# PCB_Node.net
KiCad netlist of a schematic drawn in EAGLE
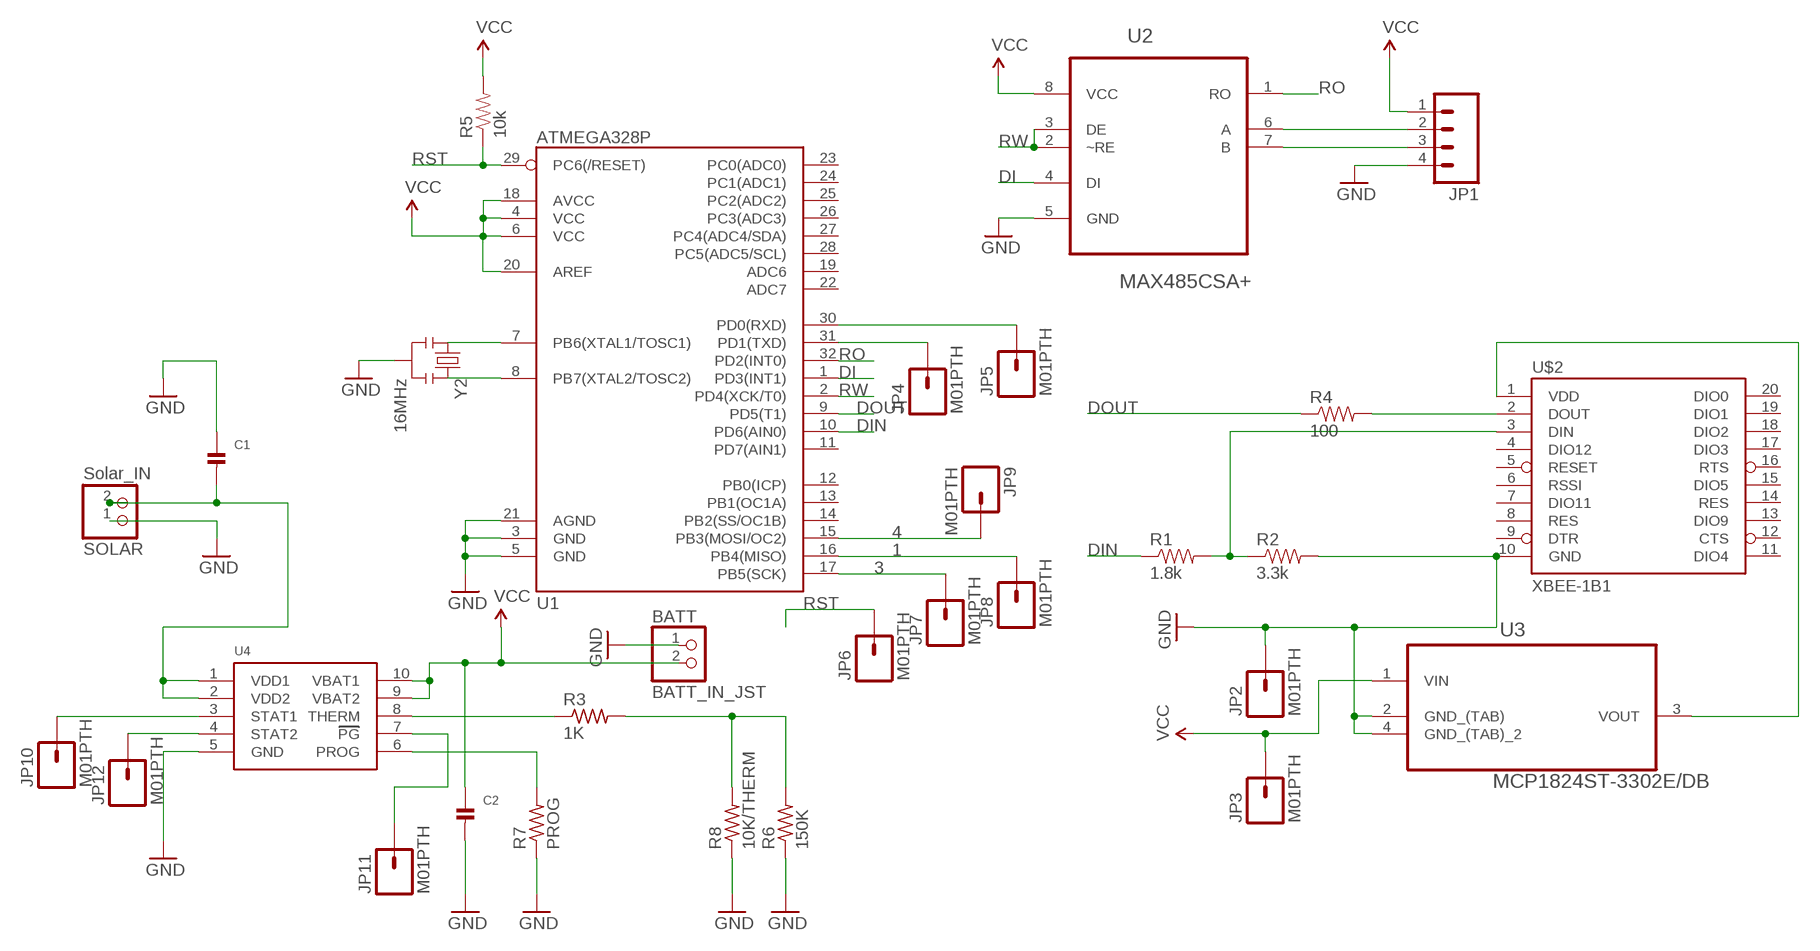
[diagram p0: schematic, sheet 1]

(export (version "E")
  (design (tool "Eeschema 10.0.6"))
  (components
    (comp (ref "BATT")
      (value "BATT_IN_JST")
      (footprint "eagle-import:JSTPH2")
      (libsource (lib "eagle-import") (part "JST_2PIN"))
    )
    (comp (ref "C1")
      (value "CAP_CERAMIC0805")
      (footprint "eagle-import:0805")
      (libsource (lib "eagle-import") (part "CAP_CERAMIC0805"))
    )
    (comp (ref "C2")
      (value "CAP_CERAMIC0805")
      (footprint "eagle-import:0805")
      (libsource (lib "eagle-import") (part "CAP_CERAMIC0805"))
    )
    (comp (ref "JP1")
      (value "M04PTH")
      (footprint "eagle-import:1X04")
      (libsource (lib "eagle-import") (part "M04PTH"))
    )
    (comp (ref "JP2")
      (value "M01PTH")
      (footprint "eagle-import:1X01")
      (libsource (lib "eagle-import") (part "M01PTH"))
    )
    (comp (ref "JP3")
      (value "M01PTH")
      (footprint "eagle-import:1X01")
      (libsource (lib "eagle-import") (part "M01PTH"))
    )
    (comp (ref "JP4")
      (value "M01PTH")
      (footprint "eagle-import:1X01")
      (libsource (lib "eagle-import") (part "M01PTH"))
    )
    (comp (ref "JP5")
      (value "M01PTH")
      (footprint "eagle-import:1X01")
      (libsource (lib "eagle-import") (part "M01PTH"))
    )
    (comp (ref "JP6")
      (value "M01PTH")
      (footprint "eagle-import:1X01")
      (libsource (lib "eagle-import") (part "M01PTH"))
    )
    (comp (ref "JP7")
      (value "M01PTH")
      (footprint "eagle-import:1X01")
      (libsource (lib "eagle-import") (part "M01PTH"))
    )
    (comp (ref "JP8")
      (value "M01PTH")
      (footprint "eagle-import:1X01")
      (libsource (lib "eagle-import") (part "M01PTH"))
    )
    (comp (ref "JP9")
      (value "M01PTH")
      (footprint "eagle-import:1X01")
      (libsource (lib "eagle-import") (part "M01PTH"))
    )
    (comp (ref "JP10")
      (value "M01PTH")
      (footprint "eagle-import:1X01")
      (libsource (lib "eagle-import") (part "M01PTH"))
    )
    (comp (ref "JP11")
      (value "M01PTH")
      (footprint "eagle-import:1X01")
      (libsource (lib "eagle-import") (part "M01PTH"))
    )
    (comp (ref "JP12")
      (value "M01PTH")
      (footprint "eagle-import:1X01")
      (libsource (lib "eagle-import") (part "M01PTH"))
    )
    (comp (ref "R1")
      (value "1.8k")
      (footprint "eagle-import:0603-RES")
      (libsource (lib "eagle-import") (part "1.8KOHM1/10W1%(0603)"))
    )
    (comp (ref "R2")
      (value "3.3k")
      (footprint "eagle-import:0603-RES")
      (libsource (lib "eagle-import") (part "3.3KOHM1/10W1%(0603)"))
    )
    (comp (ref "R3")
      (value "1K")
      (footprint "eagle-import:R0805")
      (libsource (lib "eagle-import") (part "R-US_R0805"))
    )
    (comp (ref "R4")
      (value "100")
      (footprint "eagle-import:0603-RES")
      (libsource (lib "eagle-import") (part "100OHM1/10W1%(0603)"))
    )
    (comp (ref "R5")
      (value "10k")
      (footprint "eagle-import:0603-RES")
      (libsource (lib "eagle-import") (part "10K-1%RES-00824"))
    )
    (comp (ref "R6")
      (value "150K")
      (footprint "eagle-import:R0805")
      (libsource (lib "eagle-import") (part "R-US_R0805"))
    )
    (comp (ref "R7")
      (value "PROG")
      (footprint "eagle-import:0805-THM")
      (libsource (lib "eagle-import") (part "RESISTOR_DUAL"))
    )
    (comp (ref "R8")
      (value "10K/THERM")
      (footprint "eagle-import:0805-THM")
      (libsource (lib "eagle-import") (part "R-US_FLIPFLOP"))
    )
    (comp (ref "SOLAR")
      (value "Solar_IN")
      (footprint "eagle-import:JSTPH2")
      (libsource (lib "eagle-import") (part "JST_2PIN"))
    )
    (comp (ref "U$2")
      (value "XBEE-1B1")
      (footprint "eagle-import:XBEE-1")
      (libsource (lib "eagle-import") (part "XBEE-1B1"))
    )
    (comp (ref "U1")
      (value "ATMEGA328P")
      (footprint "eagle-import:TQFP32-08")
      (libsource (lib "eagle-import") (part "ATMEGA328_SMT"))
    )
    (comp (ref "U2")
      (value "MAX485CSA+")
      (footprint "eagle-import:SOIC127P600X175-8N")
      (libsource (lib "eagle-import") (part "MAX485CSA+"))
    )
    (comp (ref "U3")
      (value "MCP1824ST-3302E/DB")
      (footprint "eagle-import:SOT230P700X180-4N")
      (libsource (lib "eagle-import") (part "MCP1824ST-3302E/DB"))
    )
    (comp (ref "U4")
      (value "MCP73833")
      (footprint "eagle-import:MSOP10")
      (libsource (lib "eagle-import") (part "MCP73833"))
    )
    (comp (ref "Y2")
      (value "16MHz")
      (footprint "eagle-import:RESONATOR-SMD")
      (libsource (lib "eagle-import") (part "RESONATOR16MHZ"))
    )
  )
  (nets
    (net (code "1") (name "/1") (class "Default")
      (node (ref "JP8") (pin "1") (pinfunction "1_1") (pintype "passive"))
      (node (ref "U1") (pin "16") (pinfunction "PB4(MISO)_16") (pintype "bidirectional"))
    )
    (net (code "2") (name "/3") (class "Default")
      (node (ref "JP7") (pin "1") (pinfunction "1_1") (pintype "passive"))
      (node (ref "U1") (pin "17") (pinfunction "PB5(SCK)_17") (pintype "bidirectional"))
    )
    (net (code "3") (name "/4") (class "Default")
      (node (ref "JP9") (pin "1") (pinfunction "1_1") (pintype "passive"))
      (node (ref "U1") (pin "15") (pinfunction "PB3(MOSI/OC2)_15") (pintype "bidirectional"))
    )
    (net (code "4") (name "/DI") (class "Default")
      (node (ref "U1") (pin "1") (pinfunction "PD3(INT1)_1") (pintype "bidirectional"))
      (node (ref "U2") (pin "4") (pinfunction "DI_4") (pintype "input"))
    )
    (net (code "5") (name "/DIN") (class "Default")
      (node (ref "R1") (pin "1") (pinfunction "1_1") (pintype "passive"))
      (node (ref "U1") (pin "10") (pinfunction "PD6(AIN0)_10") (pintype "bidirectional"))
    )
    (net (code "6") (name "/DOUT") (class "Default")
      (node (ref "R4") (pin "1") (pinfunction "1_1") (pintype "passive"))
      (node (ref "U1") (pin "9") (pinfunction "PD5(T1)_9") (pintype "bidirectional"))
    )
    (net (code "7") (name "/RO") (class "Default")
      (node (ref "U1") (pin "32") (pinfunction "PD2(INT0)_32") (pintype "bidirectional"))
      (node (ref "U2") (pin "1") (pinfunction "RO_1") (pintype "output"))
    )
    (net (code "8") (name "/RST") (class "Default")
      (node (ref "JP6") (pin "1") (pinfunction "1_1") (pintype "passive"))
      (node (ref "R5") (pin "1") (pinfunction "1_1") (pintype "passive"))
      (node (ref "U1") (pin "29") (pinfunction "PC6(/RESET)_29") (pintype "bidirectional"))
    )
    (net (code "9") (name "/RW") (class "Default")
      (node (ref "U1") (pin "2") (pinfunction "PD4(XCK/T0)_2") (pintype "bidirectional"))
      (node (ref "U2") (pin "2") (pinfunction "~{RE}_2") (pintype "input"))
      (node (ref "U2") (pin "3") (pinfunction "DE_3") (pintype "input"))
    )
    (net (code "10") (name "GND") (class "Default")
      (node (ref "BATT") (pin "1") (pinfunction "1_1") (pintype "passive"))
      (node (ref "C1") (pin "1") (pinfunction "P$1_1") (pintype "passive"))
      (node (ref "C2") (pin "2") (pinfunction "P$2_2") (pintype "passive"))
      (node (ref "JP1") (pin "4") (pinfunction "4_4") (pintype "passive"))
      (node (ref "JP2") (pin "1") (pinfunction "1_1") (pintype "passive"))
      (node (ref "R2") (pin "2") (pinfunction "2_2") (pintype "passive"))
      (node (ref "R6") (pin "1") (pinfunction "1_1") (pintype "passive"))
      (node (ref "R7") (pin "1") (pinfunction "1_1") (pintype "passive"))
      (node (ref "R8") (pin "1") (pinfunction "1_1") (pintype "passive"))
      (node (ref "SOLAR") (pin "1") (pinfunction "1_1") (pintype "passive"))
      (node (ref "U$2") (pin "10") (pinfunction "GND_10") (pintype "power_in"))
      (node (ref "U1") (pin "21") (pinfunction "AGND_21") (pintype "bidirectional"))
      (node (ref "U1") (pin "3") (pinfunction "GND_3") (pintype "bidirectional"))
      (node (ref "U1") (pin "5") (pinfunction "GND_5") (pintype "bidirectional"))
      (node (ref "U2") (pin "5") (pinfunction "GND_5") (pintype "passive"))
      (node (ref "U3") (pin "2") (pinfunction "GND_(TAB)_2") (pintype "passive"))
      (node (ref "U3") (pin "4") (pinfunction "GND_(TAB)_2_4") (pintype "passive"))
      (node (ref "U4") (pin "5") (pinfunction "GND_5") (pintype "bidirectional"))
      (node (ref "Y2") (pin "2") (pinfunction "2_2") (pintype "passive"))
    )
    (net (code "11") (name "Net-(C1-P$2)") (class "Default")
      (node (ref "C1") (pin "2") (pinfunction "P$2_2") (pintype "passive"))
      (node (ref "SOLAR") (pin "2") (pinfunction "2_2") (pintype "passive"))
      (node (ref "U4") (pin "1") (pinfunction "VDD1_1") (pintype "bidirectional"))
      (node (ref "U4") (pin "2") (pinfunction "VDD2_2") (pintype "bidirectional"))
    )
    (net (code "12") (name "Net-(R3-Pad2)") (class "Default")
      (node (ref "R3") (pin "2") (pinfunction "2_2") (pintype "passive"))
      (node (ref "R6") (pin "2") (pinfunction "2_2") (pintype "passive"))
      (node (ref "R8") (pin "2") (pinfunction "2_2") (pintype "passive"))
    )
    (net (code "13") (name "Net-(U$2-DIN)") (class "Default")
      (node (ref "R1") (pin "2") (pinfunction "2_2") (pintype "passive"))
      (node (ref "R2") (pin "1") (pinfunction "1_1") (pintype "passive"))
      (node (ref "U$2") (pin "3") (pinfunction "DIN_3") (pintype "input"))
    )
    (net (code "14") (name "Net-(U$2-DOUT)") (class "Default")
      (node (ref "R4") (pin "2") (pinfunction "2_2") (pintype "passive"))
      (node (ref "U$2") (pin "2") (pinfunction "DOUT_2") (pintype "output"))
    )
    (net (code "15") (name "Net-(U$2-VDD)") (class "Default")
      (node (ref "U$2") (pin "1") (pinfunction "VDD_1") (pintype "power_in"))
      (node (ref "U3") (pin "3") (pinfunction "VOUT_3") (pintype "output"))
    )
    (net (code "16") (name "Net-(U1-PB6(XTAL1{slash}TOSC1))") (class "Default")
      (node (ref "U1") (pin "7") (pinfunction "PB6(XTAL1/TOSC1)_7") (pintype "bidirectional"))
      (node (ref "Y2") (pin "1") (pinfunction "1_1") (pintype "passive"))
    )
    (net (code "17") (name "Net-(U1-PB7(XTAL2{slash}TOSC2))") (class "Default")
      (node (ref "U1") (pin "8") (pinfunction "PB7(XTAL2/TOSC2)_8") (pintype "bidirectional"))
      (node (ref "Y2") (pin "3") (pinfunction "3_3") (pintype "passive"))
    )
    (net (code "18") (name "Net-(U1-PD0(RXD))") (class "Default")
      (node (ref "JP5") (pin "1") (pinfunction "1_1") (pintype "passive"))
      (node (ref "U1") (pin "30") (pinfunction "PD0(RXD)_30") (pintype "bidirectional"))
    )
    (net (code "19") (name "Net-(U1-PD1(TXD))") (class "Default")
      (node (ref "JP4") (pin "1") (pinfunction "1_1") (pintype "passive"))
      (node (ref "U1") (pin "31") (pinfunction "PD1(TXD)_31") (pintype "bidirectional"))
    )
    (net (code "20") (name "Net-(U2-A)") (class "Default")
      (node (ref "JP1") (pin "2") (pinfunction "2_2") (pintype "passive"))
      (node (ref "U2") (pin "6") (pinfunction "A_6") (pintype "bidirectional"))
    )
    (net (code "21") (name "Net-(U2-B)") (class "Default")
      (node (ref "JP1") (pin "3") (pinfunction "3_3") (pintype "passive"))
      (node (ref "U2") (pin "7") (pinfunction "B_7") (pintype "bidirectional"))
    )
    (net (code "22") (name "Net-(U4-PG)") (class "Default")
      (node (ref "JP11") (pin "1") (pinfunction "1_1") (pintype "passive"))
      (node (ref "U4") (pin "7") (pinfunction "PG_7") (pintype "bidirectional"))
    )
    (net (code "23") (name "Net-(U4-PROG)") (class "Default")
      (node (ref "R7") (pin "2") (pinfunction "2_2") (pintype "passive"))
      (node (ref "U4") (pin "6") (pinfunction "PROG_6") (pintype "bidirectional"))
    )
    (net (code "24") (name "Net-(U4-STAT1)") (class "Default")
      (node (ref "JP10") (pin "1") (pinfunction "1_1") (pintype "passive"))
      (node (ref "U4") (pin "3") (pinfunction "STAT1_3") (pintype "bidirectional"))
    )
    (net (code "25") (name "Net-(U4-STAT2)") (class "Default")
      (node (ref "JP12") (pin "1") (pinfunction "1_1") (pintype "passive"))
      (node (ref "U4") (pin "4") (pinfunction "STAT2_4") (pintype "bidirectional"))
    )
    (net (code "26") (name "Net-(U4-THERM)") (class "Default")
      (node (ref "R3") (pin "1") (pinfunction "1_1") (pintype "passive"))
      (node (ref "U4") (pin "8") (pinfunction "THERM_8") (pintype "bidirectional"))
    )
    (net (code "27") (name "VCC") (class "Default")
      (node (ref "BATT") (pin "2") (pinfunction "2_2") (pintype "passive"))
      (node (ref "C2") (pin "1") (pinfunction "P$1_1") (pintype "passive"))
      (node (ref "JP1") (pin "1") (pinfunction "1_1") (pintype "passive"))
      (node (ref "JP3") (pin "1") (pinfunction "1_1") (pintype "passive"))
      (node (ref "R5") (pin "2") (pinfunction "2_2") (pintype "passive"))
      (node (ref "U1") (pin "18") (pinfunction "AVCC_18") (pintype "bidirectional"))
      (node (ref "U1") (pin "20") (pinfunction "AREF_20") (pintype "bidirectional"))
      (node (ref "U1") (pin "4") (pinfunction "VCC_4") (pintype "bidirectional"))
      (node (ref "U1") (pin "6") (pinfunction "VCC_6") (pintype "bidirectional"))
      (node (ref "U2") (pin "8") (pinfunction "VCC_8") (pintype "power_in"))
      (node (ref "U3") (pin "1") (pinfunction "VIN_1") (pintype "input"))
      (node (ref "U4") (pin "10") (pinfunction "VBAT1_10") (pintype "bidirectional"))
      (node (ref "U4") (pin "9") (pinfunction "VBAT2_9") (pintype "bidirectional"))
    )
    (net (code "28") (name "unconnected-(U$2-CTS-Pad12)") (class "Default")
      (node (ref "U$2") (pin "12") (pinfunction "CTS_12") (pintype "output"))
    )
    (net (code "29") (name "unconnected-(U$2-DIO0-Pad20)") (class "Default")
      (node (ref "U$2") (pin "20") (pinfunction "DIO0_20") (pintype "bidirectional"))
    )
    (net (code "30") (name "unconnected-(U$2-DIO1-Pad19)") (class "Default")
      (node (ref "U$2") (pin "19") (pinfunction "DIO1_19") (pintype "bidirectional"))
    )
    (net (code "31") (name "unconnected-(U$2-DIO2-Pad18)") (class "Default")
      (node (ref "U$2") (pin "18") (pinfunction "DIO2_18") (pintype "bidirectional"))
    )
    (net (code "32") (name "unconnected-(U$2-DIO3-Pad17)") (class "Default")
      (node (ref "U$2") (pin "17") (pinfunction "DIO3_17") (pintype "bidirectional"))
    )
    (net (code "33") (name "unconnected-(U$2-DIO4-Pad11)") (class "Default")
      (node (ref "U$2") (pin "11") (pinfunction "DIO4_11") (pintype "bidirectional"))
    )
    (net (code "34") (name "unconnected-(U$2-DIO5-Pad15)") (class "Default")
      (node (ref "U$2") (pin "15") (pinfunction "DIO5_15") (pintype "bidirectional"))
    )
    (net (code "35") (name "unconnected-(U$2-DIO9-Pad13)") (class "Default")
      (node (ref "U$2") (pin "13") (pinfunction "DIO9_13") (pintype "bidirectional"))
    )
    (net (code "36") (name "unconnected-(U$2-DIO11-Pad7)") (class "Default")
      (node (ref "U$2") (pin "7") (pinfunction "DIO11_7") (pintype "bidirectional"))
    )
    (net (code "37") (name "unconnected-(U$2-DIO12-Pad4)") (class "Default")
      (node (ref "U$2") (pin "4") (pinfunction "DIO12_4") (pintype "bidirectional"))
    )
    (net (code "38") (name "unconnected-(U$2-DTR-Pad9)") (class "Default")
      (node (ref "U$2") (pin "9") (pinfunction "DTR_9") (pintype "bidirectional"))
    )
    (net (code "39") (name "unconnected-(U$2-RES-Pad8)") (class "Default")
      (node (ref "U$2") (pin "8") (pinfunction "RES_8") (pintype "bidirectional"))
    )
    (net (code "40") (name "unconnected-(U$2-RES-Pad14)") (class "Default")
      (node (ref "U$2") (pin "14") (pinfunction "RES_14") (pintype "bidirectional"))
    )
    (net (code "41") (name "unconnected-(U$2-RESET-Pad5)") (class "Default")
      (node (ref "U$2") (pin "5") (pinfunction "RESET_5") (pintype "input"))
    )
    (net (code "42") (name "unconnected-(U$2-RSSI-Pad6)") (class "Default")
      (node (ref "U$2") (pin "6") (pinfunction "RSSI_6") (pintype "bidirectional"))
    )
    (net (code "43") (name "unconnected-(U$2-RTS-Pad16)") (class "Default")
      (node (ref "U$2") (pin "16") (pinfunction "RTS_16") (pintype "input"))
    )
    (net (code "44") (name "unconnected-(U1-ADC6-Pad19)") (class "Default")
      (node (ref "U1") (pin "19") (pinfunction "ADC6_19") (pintype "bidirectional"))
    )
    (net (code "45") (name "unconnected-(U1-ADC7-Pad22)") (class "Default")
      (node (ref "U1") (pin "22") (pinfunction "ADC7_22") (pintype "bidirectional"))
    )
    (net (code "46") (name "unconnected-(U1-PB0(ICP)-Pad12)") (class "Default")
      (node (ref "U1") (pin "12") (pinfunction "PB0(ICP)_12") (pintype "bidirectional"))
    )
    (net (code "47") (name "unconnected-(U1-PB1(OC1A)-Pad13)") (class "Default")
      (node (ref "U1") (pin "13") (pinfunction "PB1(OC1A)_13") (pintype "bidirectional"))
    )
    (net (code "48") (name "unconnected-(U1-PB2(SS{slash}OC1B)-Pad14)") (class "Default")
      (node (ref "U1") (pin "14") (pinfunction "PB2(SS/OC1B)_14") (pintype "bidirectional"))
    )
    (net (code "49") (name "unconnected-(U1-PC0(ADC0)-Pad23)") (class "Default")
      (node (ref "U1") (pin "23") (pinfunction "PC0(ADC0)_23") (pintype "bidirectional"))
    )
    (net (code "50") (name "unconnected-(U1-PC1(ADC1)-Pad24)") (class "Default")
      (node (ref "U1") (pin "24") (pinfunction "PC1(ADC1)_24") (pintype "bidirectional"))
    )
    (net (code "51") (name "unconnected-(U1-PC2(ADC2)-Pad25)") (class "Default")
      (node (ref "U1") (pin "25") (pinfunction "PC2(ADC2)_25") (pintype "bidirectional"))
    )
    (net (code "52") (name "unconnected-(U1-PC3(ADC3)-Pad26)") (class "Default")
      (node (ref "U1") (pin "26") (pinfunction "PC3(ADC3)_26") (pintype "bidirectional"))
    )
    (net (code "53") (name "unconnected-(U1-PC4(ADC4{slash}SDA)-Pad27)") (class "Default")
      (node (ref "U1") (pin "27") (pinfunction "PC4(ADC4/SDA)_27") (pintype "bidirectional"))
    )
    (net (code "54") (name "unconnected-(U1-PC5(ADC5{slash}SCL)-Pad28)") (class "Default")
      (node (ref "U1") (pin "28") (pinfunction "PC5(ADC5/SCL)_28") (pintype "bidirectional"))
    )
    (net (code "55") (name "unconnected-(U1-PD7(AIN1)-Pad11)") (class "Default")
      (node (ref "U1") (pin "11") (pinfunction "PD7(AIN1)_11") (pintype "bidirectional"))
    )
  )
)
